# AirBee.net
KiCad netlist of a schematic drawn in Altium Designer
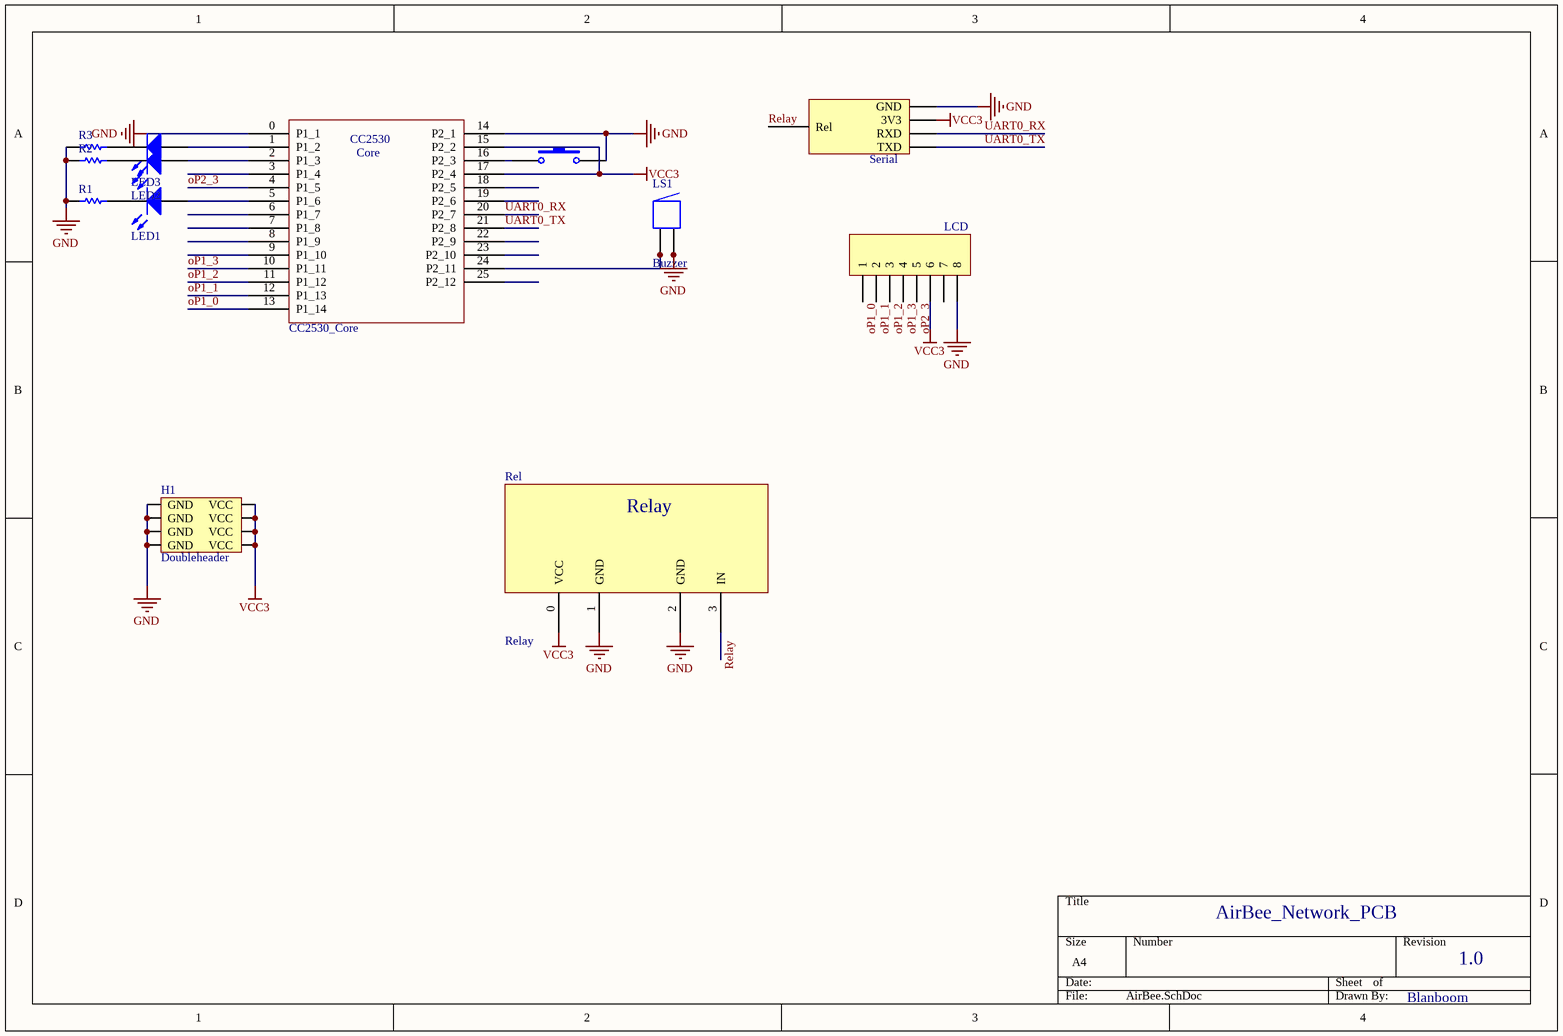
[diagram p0: AirBee.SchDoc]

(export (version "E")
  (design (tool "Eeschema 10.0.6"))
  (components
    (comp (ref "2530")
      (value "CC2530_Core")
      (footprint "CC2530_Core")
      (libsource (lib "AirBee") (part "CC2530_Core"))
    )
    (comp (ref "D1")
      (value "LED1")
      (footprint "LED")
      (description "Typical INFRARED GaAs LED")
      (fields (field (name "PUBLISHER") "Altium Limited"))
      (libsource (lib "Miscellaneous Devices") (part "LED0"))
    )
    (comp (ref "D2")
      (value "LED2")
      (footprint "LED")
      (description "Typical INFRARED GaAs LED")
      (fields (field (name "PUBLISHER") "Altium Limited"))
      (libsource (lib "Miscellaneous Devices") (part "LED0"))
    )
    (comp (ref "D3")
      (value "LED3")
      (footprint "LED")
      (description "Typical INFRARED GaAs LED")
      (fields (field (name "PUBLISHER") "Altium Limited"))
      (libsource (lib "Miscellaneous Devices") (part "LED0"))
    )
    (comp (ref "H1")
      (value "Doubleheader")
      (footprint "header16")
      (libsource (lib "AirBee") (part "Doubleheader"))
    )
    (comp (ref "LCD") (value "HEAder8") (footprint "header8") (libsource (lib "MyLib") (part "HEAder8")))
    (comp (ref "LS1")
      (value "Buzzer")
      (footprint "5V-BUZZER")
      (description "Magnetic Transducer Buzzer")
      (fields (field (name "PUBLISHER") "Altium Limited"))
      (libsource (lib "Miscellaneous Devices") (part "Buzzer"))
    )
    (comp (ref "R1")
      (value "Res")
      (footprint "AXIAL-0.3")
      (description "Resistor")
      (fields (field (name "PUBLISHER") "Altium Limited"))
      (libsource (lib "Miscellaneous Devices") (part "Res1"))
    )
    (comp (ref "R2")
      (value "Res")
      (footprint "AXIAL-0.3")
      (description "Resistor")
      (fields (field (name "PUBLISHER") "Altium Limited"))
      (libsource (lib "Miscellaneous Devices") (part "Res1"))
    )
    (comp (ref "R3")
      (value "Res")
      (footprint "AXIAL-0.3")
      (description "Resistor")
      (fields (field (name "PUBLISHER") "Altium Limited"))
      (libsource (lib "Miscellaneous Devices") (part "Res1"))
    )
    (comp (ref "Rel") (value "Relay") (footprint "Relay") (libsource (lib "AirBee") (part "Relay")))
    (comp (ref "Reset") (value "Switch") (footprint "微动开关") (libsource (lib "AirBee") (part "Switch")))
    (comp (ref "Serial") (value "Serial") (footprint "header5") (libsource (lib "AirBee") (part "Serial")))
  )
  (nets
    (net (code "1") (name "/Relay") (class "Default")
      (node (ref "Rel") (pin "3") (pinfunction "IN_3") (pintype "passive"))
      (node (ref "Serial") (pin "5") (pinfunction "Rel_5") (pintype "passive"))
    )
    (net (code "2") (name "/UART0_RX") (class "Default")
      (node (ref "2530") (pin "20") (pinfunction "P2_7_20") (pintype "passive"))
      (node (ref "Serial") (pin "2") (pinfunction "RXD_2") (pintype "passive"))
    )
    (net (code "3") (name "/UART0_TX") (class "Default")
      (node (ref "2530") (pin "21") (pinfunction "P2_8_21") (pintype "passive"))
      (node (ref "Serial") (pin "1") (pinfunction "TXD_1") (pintype "passive"))
    )
    (net (code "4") (name "/oP1_0") (class "Default")
      (node (ref "2530") (pin "13") (pinfunction "P1_14_13") (pintype "passive"))
      (node (ref "LCD") (pin "1") (pinfunction "1_1") (pintype "passive"))
    )
    (net (code "5") (name "/oP1_1") (class "Default")
      (node (ref "2530") (pin "12") (pinfunction "P1_13_12") (pintype "passive"))
      (node (ref "LCD") (pin "2") (pinfunction "2_2") (pintype "passive"))
    )
    (net (code "6") (name "/oP1_2") (class "Default")
      (node (ref "2530") (pin "11") (pinfunction "P1_12_11") (pintype "passive"))
      (node (ref "LCD") (pin "3") (pinfunction "3_3") (pintype "passive"))
    )
    (net (code "7") (name "/oP1_3") (class "Default")
      (node (ref "2530") (pin "10") (pinfunction "P1_11_10") (pintype "passive"))
      (node (ref "LCD") (pin "4") (pinfunction "4_4") (pintype "passive"))
    )
    (net (code "8") (name "/oP2_3") (class "Default")
      (node (ref "2530") (pin "4") (pinfunction "P1_5_4") (pintype "passive"))
      (node (ref "LCD") (pin "5") (pinfunction "5_5") (pintype "passive"))
    )
    (net (code "9") (name "GND") (class "Default")
      (node (ref "2530") (pin "0") (pinfunction "P1_1_0") (pintype "passive"))
      (node (ref "2530") (pin "14") (pinfunction "P2_1_14") (pintype "passive"))
      (node (ref "H1") (pin "1") (pinfunction "GND_1") (pintype "passive"))
      (node (ref "H1") (pin "2") (pinfunction "GND_2") (pintype "passive"))
      (node (ref "H1") (pin "3") (pinfunction "GND_3") (pintype "passive"))
      (node (ref "H1") (pin "4") (pinfunction "GND_4") (pintype "passive"))
      (node (ref "LCD") (pin "8") (pinfunction "8_8") (pintype "passive"))
      (node (ref "LS1") (pin "2") (pinfunction "2_2") (pintype "passive"))
      (node (ref "LS1") (pin "2A") (pinfunction "2A_2A") (pintype "passive"))
      (node (ref "R1") (pin "1") (pinfunction "1_1") (pintype "passive"))
      (node (ref "R2") (pin "1") (pinfunction "1_1") (pintype "passive"))
      (node (ref "R3") (pin "1") (pinfunction "1_1") (pintype "passive"))
      (node (ref "Rel") (pin "1") (pinfunction "GND_1") (pintype "passive"))
      (node (ref "Rel") (pin "2") (pinfunction "GND_2") (pintype "passive"))
      (node (ref "Reset") (pin "2") (pinfunction "2_2") (pintype "passive"))
      (node (ref "Serial") (pin "4") (pinfunction "GND_4") (pintype "passive"))
    )
    (net (code "10") (name "Net-(2530-P1_2)") (class "Default")
      (node (ref "2530") (pin "1") (pinfunction "P1_2_1") (pintype "passive"))
      (node (ref "D3") (pin "1") (pinfunction "A_1") (pintype "passive"))
    )
    (net (code "11") (name "Net-(2530-P1_3)") (class "Default")
      (node (ref "2530") (pin "2") (pinfunction "P1_3_2") (pintype "passive"))
      (node (ref "D2") (pin "1") (pinfunction "A_1") (pintype "passive"))
    )
    (net (code "12") (name "Net-(2530-P1_6)") (class "Default")
      (node (ref "2530") (pin "5") (pinfunction "P1_6_5") (pintype "passive"))
      (node (ref "D1") (pin "1") (pinfunction "A_1") (pintype "passive"))
    )
    (net (code "13") (name "Net-(2530-P2_3)") (class "Default")
      (node (ref "2530") (pin "16") (pinfunction "P2_3_16") (pintype "passive"))
      (node (ref "Reset") (pin "1") (pinfunction "1_1") (pintype "passive"))
    )
    (net (code "14") (name "Net-(2530-P2_11)") (class "Default")
      (node (ref "2530") (pin "24") (pinfunction "P2_11_24") (pintype "passive"))
      (node (ref "LS1") (pin "1") (pinfunction "1_1") (pintype "passive"))
      (node (ref "LS1") (pin "1A") (pinfunction "1A_1A") (pintype "passive"))
    )
    (net (code "15") (name "Net-(D1-K)") (class "Default")
      (node (ref "D1") (pin "2") (pinfunction "K_2") (pintype "passive"))
      (node (ref "R1") (pin "2") (pinfunction "2_2") (pintype "passive"))
    )
    (net (code "16") (name "Net-(D2-K)") (class "Default")
      (node (ref "D2") (pin "2") (pinfunction "K_2") (pintype "passive"))
      (node (ref "R2") (pin "2") (pinfunction "2_2") (pintype "passive"))
    )
    (net (code "17") (name "Net-(D3-K)") (class "Default")
      (node (ref "D3") (pin "2") (pinfunction "K_2") (pintype "passive"))
      (node (ref "R3") (pin "2") (pinfunction "2_2") (pintype "passive"))
    )
    (net (code "18") (name "VCC3") (class "Default")
      (node (ref "2530") (pin "15") (pinfunction "P2_2_15") (pintype "passive"))
      (node (ref "2530") (pin "17") (pinfunction "P2_4_17") (pintype "passive"))
      (node (ref "H1") (pin "5") (pinfunction "VCC_5") (pintype "passive"))
      (node (ref "H1") (pin "6") (pinfunction "VCC_6") (pintype "passive"))
      (node (ref "H1") (pin "7") (pinfunction "VCC_7") (pintype "passive"))
      (node (ref "H1") (pin "8") (pinfunction "VCC_8") (pintype "passive"))
      (node (ref "LCD") (pin "6") (pinfunction "6_6") (pintype "passive"))
      (node (ref "Rel") (pin "0") (pinfunction "VCC_0") (pintype "passive"))
      (node (ref "Serial") (pin "3") (pinfunction "3V3_3") (pintype "passive"))
    )
    (net (code "19") (name "unconnected-(2530-P1_4-Pad3)") (class "Default")
      (node (ref "2530") (pin "3") (pinfunction "P1_4_3") (pintype "passive"))
    )
    (net (code "20") (name "unconnected-(2530-P1_7-Pad6)") (class "Default")
      (node (ref "2530") (pin "6") (pinfunction "P1_7_6") (pintype "passive"))
    )
    (net (code "21") (name "unconnected-(2530-P1_8-Pad7)") (class "Default")
      (node (ref "2530") (pin "7") (pinfunction "P1_8_7") (pintype "passive"))
    )
    (net (code "22") (name "unconnected-(2530-P1_9-Pad8)") (class "Default")
      (node (ref "2530") (pin "8") (pinfunction "P1_9_8") (pintype "passive"))
    )
    (net (code "23") (name "unconnected-(2530-P1_10-Pad9)") (class "Default")
      (node (ref "2530") (pin "9") (pinfunction "P1_10_9") (pintype "passive"))
    )
    (net (code "24") (name "unconnected-(2530-P2_5-Pad18)") (class "Default")
      (node (ref "2530") (pin "18") (pinfunction "P2_5_18") (pintype "passive"))
    )
    (net (code "25") (name "unconnected-(2530-P2_6-Pad19)") (class "Default")
      (node (ref "2530") (pin "19") (pinfunction "P2_6_19") (pintype "passive"))
    )
    (net (code "26") (name "unconnected-(2530-P2_9-Pad22)") (class "Default")
      (node (ref "2530") (pin "22") (pinfunction "P2_9_22") (pintype "passive"))
    )
    (net (code "27") (name "unconnected-(2530-P2_10-Pad23)") (class "Default")
      (node (ref "2530") (pin "23") (pinfunction "P2_10_23") (pintype "passive"))
    )
    (net (code "28") (name "unconnected-(2530-P2_12-Pad25)") (class "Default")
      (node (ref "2530") (pin "25") (pinfunction "P2_12_25") (pintype "passive"))
    )
    (net (code "29") (name "unconnected-(LCD-Pad7)") (class "Default")
      (node (ref "LCD") (pin "7") (pinfunction "7_7") (pintype "passive"))
    )
  )
)
